# bare_bones_arduino.net
KiCad netlist of a schematic drawn in EAGLE
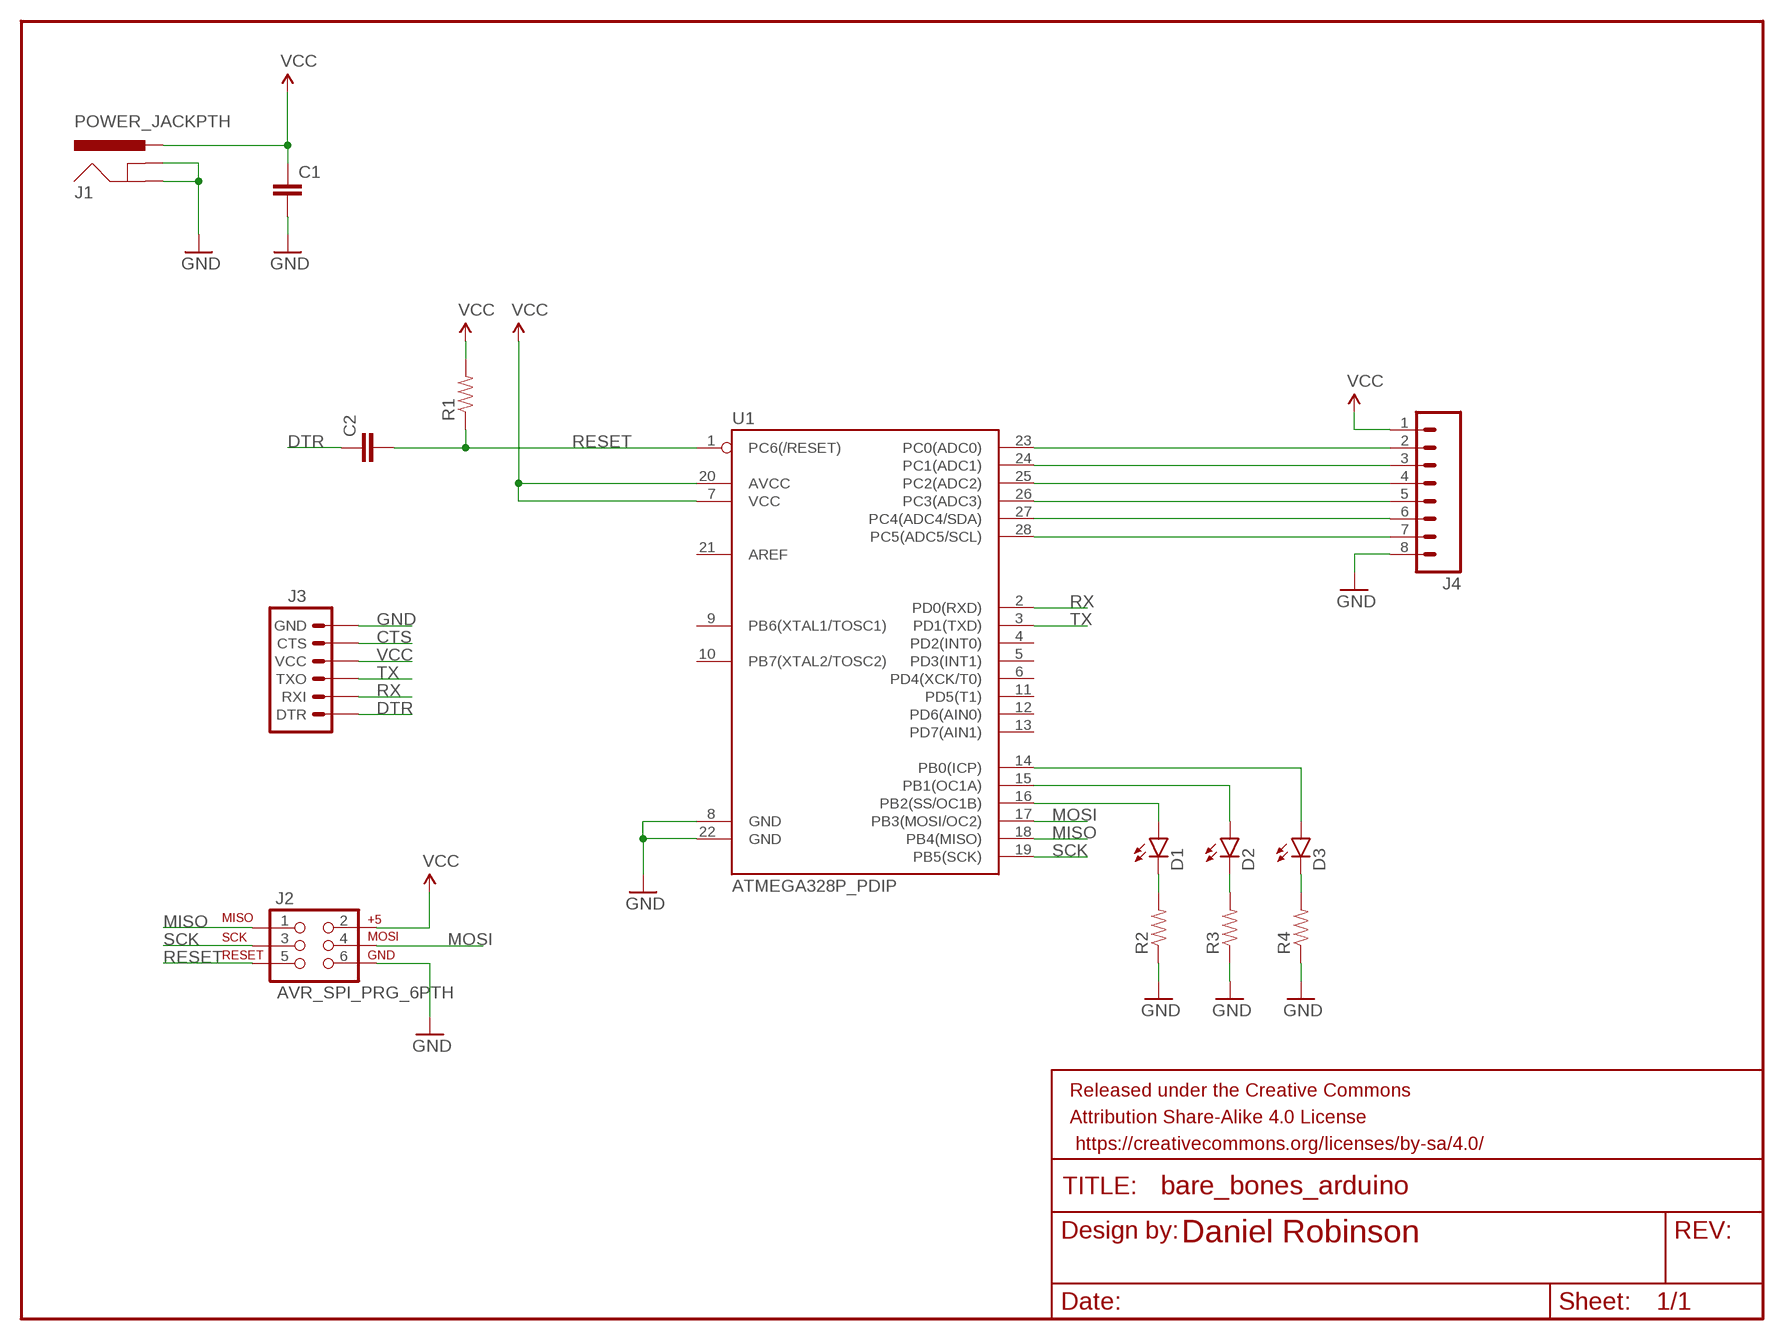
[diagram p0: schematic, sheet 1]

(export (version "E")
  (design (tool "Eeschema 10.0.6"))
  (components
    (comp (ref "C1")
      (value "CAPPTH")
      (footprint "eagle-import:CAP-PTH-SMALL")
      (libsource (lib "eagle-import") (part "SparkFun-Passives_CAPPTH"))
    )
    (comp (ref "C2")
      (value "CAPPTH")
      (footprint "eagle-import:CAP-PTH-SMALL")
      (libsource (lib "eagle-import") (part "CAPPTH"))
    )
    (comp (ref "D1")
      (value "LED5MM")
      (footprint "eagle-import:LED5MM")
      (libsource (lib "eagle-import") (part "LED5MM"))
    )
    (comp (ref "D2")
      (value "LED5MM")
      (footprint "eagle-import:LED5MM")
      (libsource (lib "eagle-import") (part "LED5MM"))
    )
    (comp (ref "D3")
      (value "LED5MM")
      (footprint "eagle-import:LED5MM")
      (libsource (lib "eagle-import") (part "LED5MM"))
    )
    (comp (ref "FRAME1")
      (value "FRAME-LETTER")
      (footprint "eagle-import:CREATIVE_COMMONS")
      (libsource (lib "eagle-import") (part "FRAME-LETTER"))
    )
    (comp (ref "J1")
      (value "POWER_JACKPTH")
      (footprint "eagle-import:POWER_JACK_PTH")
      (libsource (lib "eagle-import") (part "POWER_JACKPTH"))
    )
    (comp (ref "J2")
      (value "AVR_SPI_PRG_6PTH")
      (footprint "eagle-import:2X3")
      (libsource (lib "eagle-import") (part "AVR_SPI_PRG_6PTH"))
    )
    (comp (ref "J3")
      (value "ARDUINO_SERIAL_PROGRAMPTH")
      (footprint "eagle-import:1X06")
      (libsource (lib "eagle-import") (part "ARDUINO_SERIAL_PROGRAMPTH"))
    )
    (comp (ref "J4")
      (value "M08SILK_FEMALE_PTH")
      (footprint "eagle-import:1X08")
      (libsource (lib "eagle-import") (part "M08SILK_FEMALE_PTH"))
    )
    (comp (ref "R1")
      (value "RESISTORPTH-1/4W")
      (footprint "eagle-import:AXIAL-0.4")
      (libsource (lib "eagle-import") (part "RESISTORPTH-1/4W"))
    )
    (comp (ref "R2")
      (value "RESISTORPTH-1/4W")
      (footprint "eagle-import:AXIAL-0.4")
      (libsource (lib "eagle-import") (part "RESISTORPTH-1/4W"))
    )
    (comp (ref "R3")
      (value "RESISTORPTH-1/4W")
      (footprint "eagle-import:AXIAL-0.4")
      (libsource (lib "eagle-import") (part "RESISTORPTH-1/4W"))
    )
    (comp (ref "R4")
      (value "RESISTORPTH-1/4W")
      (footprint "eagle-import:AXIAL-0.4")
      (libsource (lib "eagle-import") (part "RESISTORPTH-1/4W"))
    )
    (comp (ref "U1")
      (value "ATMEGA328P_PDIP")
      (footprint "eagle-import:DIL28-3")
      (libsource (lib "eagle-import") (part "ATMEGA328P_PDIP"))
    )
  )
  (nets
    (net (code "1") (name "/CTS") (class "Default")
      (node (ref "J3") (pin "5") (pinfunction "CTS_5") (pintype "passive"))
    )
    (net (code "2") (name "/DTR") (class "Default")
      (node (ref "C2") (pin "1") (pinfunction "1_1") (pintype "passive"))
      (node (ref "J3") (pin "1") (pinfunction "DTR_1") (pintype "passive"))
    )
    (net (code "3") (name "/MISO") (class "Default")
      (node (ref "J2") (pin "1") (pinfunction "1_1") (pintype "passive"))
      (node (ref "U1") (pin "18") (pinfunction "PB4(MISO)_18") (pintype "bidirectional"))
    )
    (net (code "4") (name "/MOSI") (class "Default")
      (node (ref "J2") (pin "4") (pinfunction "4_4") (pintype "passive"))
      (node (ref "U1") (pin "17") (pinfunction "PB3(MOSI/OC2)_17") (pintype "bidirectional"))
    )
    (net (code "5") (name "/RESET") (class "Default")
      (node (ref "C2") (pin "2") (pinfunction "2_2") (pintype "passive"))
      (node (ref "J2") (pin "5") (pinfunction "5_5") (pintype "passive"))
      (node (ref "R1") (pin "P$1") (pinfunction "1_P$1") (pintype "passive"))
      (node (ref "U1") (pin "1") (pinfunction "PC6(/RESET)_1") (pintype "bidirectional"))
    )
    (net (code "6") (name "/RX") (class "Default")
      (node (ref "J3") (pin "2") (pinfunction "RXI_2") (pintype "passive"))
      (node (ref "U1") (pin "2") (pinfunction "PD0(RXD)_2") (pintype "bidirectional"))
    )
    (net (code "7") (name "/SCK") (class "Default")
      (node (ref "J2") (pin "3") (pinfunction "3_3") (pintype "passive"))
      (node (ref "U1") (pin "19") (pinfunction "PB5(SCK)_19") (pintype "bidirectional"))
    )
    (net (code "8") (name "/TX") (class "Default")
      (node (ref "J3") (pin "3") (pinfunction "TXO_3") (pintype "passive"))
      (node (ref "U1") (pin "3") (pinfunction "PD1(TXD)_3") (pintype "bidirectional"))
    )
    (net (code "9") (name "GND") (class "Default")
      (node (ref "C1") (pin "2") (pinfunction "2_2") (pintype "passive"))
      (node (ref "J1") (pin "GND") (pinfunction "GND_GND") (pintype "bidirectional"))
      (node (ref "J1") (pin "GNDBREAK") (pinfunction "GNDBREAK_GNDBREAK") (pintype "bidirectional"))
      (node (ref "J2") (pin "6") (pinfunction "6_6") (pintype "passive"))
      (node (ref "J3") (pin "6") (pinfunction "GND_6") (pintype "passive"))
      (node (ref "J4") (pin "8") (pinfunction "8_8") (pintype "passive"))
      (node (ref "R2") (pin "P$1") (pinfunction "1_P$1") (pintype "passive"))
      (node (ref "R3") (pin "P$1") (pinfunction "1_P$1") (pintype "passive"))
      (node (ref "R4") (pin "P$1") (pinfunction "1_P$1") (pintype "passive"))
      (node (ref "U1") (pin "22") (pinfunction "GND_22") (pintype "bidirectional"))
      (node (ref "U1") (pin "8") (pinfunction "GND_8") (pintype "bidirectional"))
    )
    (net (code "10") (name "Net-(D1-C)") (class "Default")
      (node (ref "D1") (pin "K") (pinfunction "C_K") (pintype "passive"))
      (node (ref "R2") (pin "P$2") (pinfunction "2_P$2") (pintype "passive"))
    )
    (net (code "11") (name "Net-(D2-C)") (class "Default")
      (node (ref "D2") (pin "K") (pinfunction "C_K") (pintype "passive"))
      (node (ref "R3") (pin "P$2") (pinfunction "2_P$2") (pintype "passive"))
    )
    (net (code "12") (name "Net-(D3-C)") (class "Default")
      (node (ref "D3") (pin "K") (pinfunction "C_K") (pintype "passive"))
      (node (ref "R4") (pin "P$2") (pinfunction "2_P$2") (pintype "passive"))
    )
    (net (code "13") (name "Net-(U1-PB0(ICP))") (class "Default")
      (node (ref "D3") (pin "A") (pinfunction "A_A") (pintype "passive"))
      (node (ref "U1") (pin "14") (pinfunction "PB0(ICP)_14") (pintype "bidirectional"))
    )
    (net (code "14") (name "Net-(U1-PB1(OC1A))") (class "Default")
      (node (ref "D2") (pin "A") (pinfunction "A_A") (pintype "passive"))
      (node (ref "U1") (pin "15") (pinfunction "PB1(OC1A)_15") (pintype "bidirectional"))
    )
    (net (code "15") (name "Net-(U1-PB2(SS{slash}OC1B))") (class "Default")
      (node (ref "D1") (pin "A") (pinfunction "A_A") (pintype "passive"))
      (node (ref "U1") (pin "16") (pinfunction "PB2(SS/OC1B)_16") (pintype "bidirectional"))
    )
    (net (code "16") (name "Net-(U1-PC0(ADC0))") (class "Default")
      (node (ref "J4") (pin "2") (pinfunction "2_2") (pintype "passive"))
      (node (ref "U1") (pin "23") (pinfunction "PC0(ADC0)_23") (pintype "bidirectional"))
    )
    (net (code "17") (name "Net-(U1-PC1(ADC1))") (class "Default")
      (node (ref "J4") (pin "3") (pinfunction "3_3") (pintype "passive"))
      (node (ref "U1") (pin "24") (pinfunction "PC1(ADC1)_24") (pintype "bidirectional"))
    )
    (net (code "18") (name "Net-(U1-PC2(ADC2))") (class "Default")
      (node (ref "J4") (pin "4") (pinfunction "4_4") (pintype "passive"))
      (node (ref "U1") (pin "25") (pinfunction "PC2(ADC2)_25") (pintype "bidirectional"))
    )
    (net (code "19") (name "Net-(U1-PC3(ADC3))") (class "Default")
      (node (ref "J4") (pin "5") (pinfunction "5_5") (pintype "passive"))
      (node (ref "U1") (pin "26") (pinfunction "PC3(ADC3)_26") (pintype "bidirectional"))
    )
    (net (code "20") (name "Net-(U1-PC4(ADC4{slash}SDA))") (class "Default")
      (node (ref "J4") (pin "6") (pinfunction "6_6") (pintype "passive"))
      (node (ref "U1") (pin "27") (pinfunction "PC4(ADC4/SDA)_27") (pintype "bidirectional"))
    )
    (net (code "21") (name "Net-(U1-PC5(ADC5{slash}SCL))") (class "Default")
      (node (ref "J4") (pin "7") (pinfunction "7_7") (pintype "passive"))
      (node (ref "U1") (pin "28") (pinfunction "PC5(ADC5/SCL)_28") (pintype "bidirectional"))
    )
    (net (code "22") (name "VCC") (class "Default")
      (node (ref "C1") (pin "1") (pinfunction "1_1") (pintype "passive"))
      (node (ref "J1") (pin "PWR") (pinfunction "PWR_PWR") (pintype "bidirectional"))
      (node (ref "J2") (pin "2") (pinfunction "2_2") (pintype "passive"))
      (node (ref "J3") (pin "4") (pinfunction "VCC_4") (pintype "passive"))
      (node (ref "J4") (pin "1") (pinfunction "1_1") (pintype "passive"))
      (node (ref "R1") (pin "P$2") (pinfunction "2_P$2") (pintype "passive"))
      (node (ref "U1") (pin "20") (pinfunction "AVCC_20") (pintype "bidirectional"))
      (node (ref "U1") (pin "7") (pinfunction "VCC_7") (pintype "bidirectional"))
    )
    (net (code "23") (name "unconnected-(U1-AREF-Pad21)") (class "Default")
      (node (ref "U1") (pin "21") (pinfunction "AREF_21") (pintype "bidirectional"))
    )
    (net (code "24") (name "unconnected-(U1-PB6(XTAL1{slash}TOSC1)-Pad9)") (class "Default")
      (node (ref "U1") (pin "9") (pinfunction "PB6(XTAL1/TOSC1)_9") (pintype "bidirectional"))
    )
    (net (code "25") (name "unconnected-(U1-PB7(XTAL2{slash}TOSC2)-Pad10)") (class "Default")
      (node (ref "U1") (pin "10") (pinfunction "PB7(XTAL2/TOSC2)_10") (pintype "bidirectional"))
    )
    (net (code "26") (name "unconnected-(U1-PD2(INT0)-Pad4)") (class "Default")
      (node (ref "U1") (pin "4") (pinfunction "PD2(INT0)_4") (pintype "bidirectional"))
    )
    (net (code "27") (name "unconnected-(U1-PD3(INT1)-Pad5)") (class "Default")
      (node (ref "U1") (pin "5") (pinfunction "PD3(INT1)_5") (pintype "bidirectional"))
    )
    (net (code "28") (name "unconnected-(U1-PD4(XCK{slash}T0)-Pad6)") (class "Default")
      (node (ref "U1") (pin "6") (pinfunction "PD4(XCK/T0)_6") (pintype "bidirectional"))
    )
    (net (code "29") (name "unconnected-(U1-PD5(T1)-Pad11)") (class "Default")
      (node (ref "U1") (pin "11") (pinfunction "PD5(T1)_11") (pintype "bidirectional"))
    )
    (net (code "30") (name "unconnected-(U1-PD6(AIN0)-Pad12)") (class "Default")
      (node (ref "U1") (pin "12") (pinfunction "PD6(AIN0)_12") (pintype "bidirectional"))
    )
    (net (code "31") (name "unconnected-(U1-PD7(AIN1)-Pad13)") (class "Default")
      (node (ref "U1") (pin "13") (pinfunction "PD7(AIN1)_13") (pintype "bidirectional"))
    )
  )
)
